# con68k-led.net
KiCad netlist of a schematic drawn in EAGLE
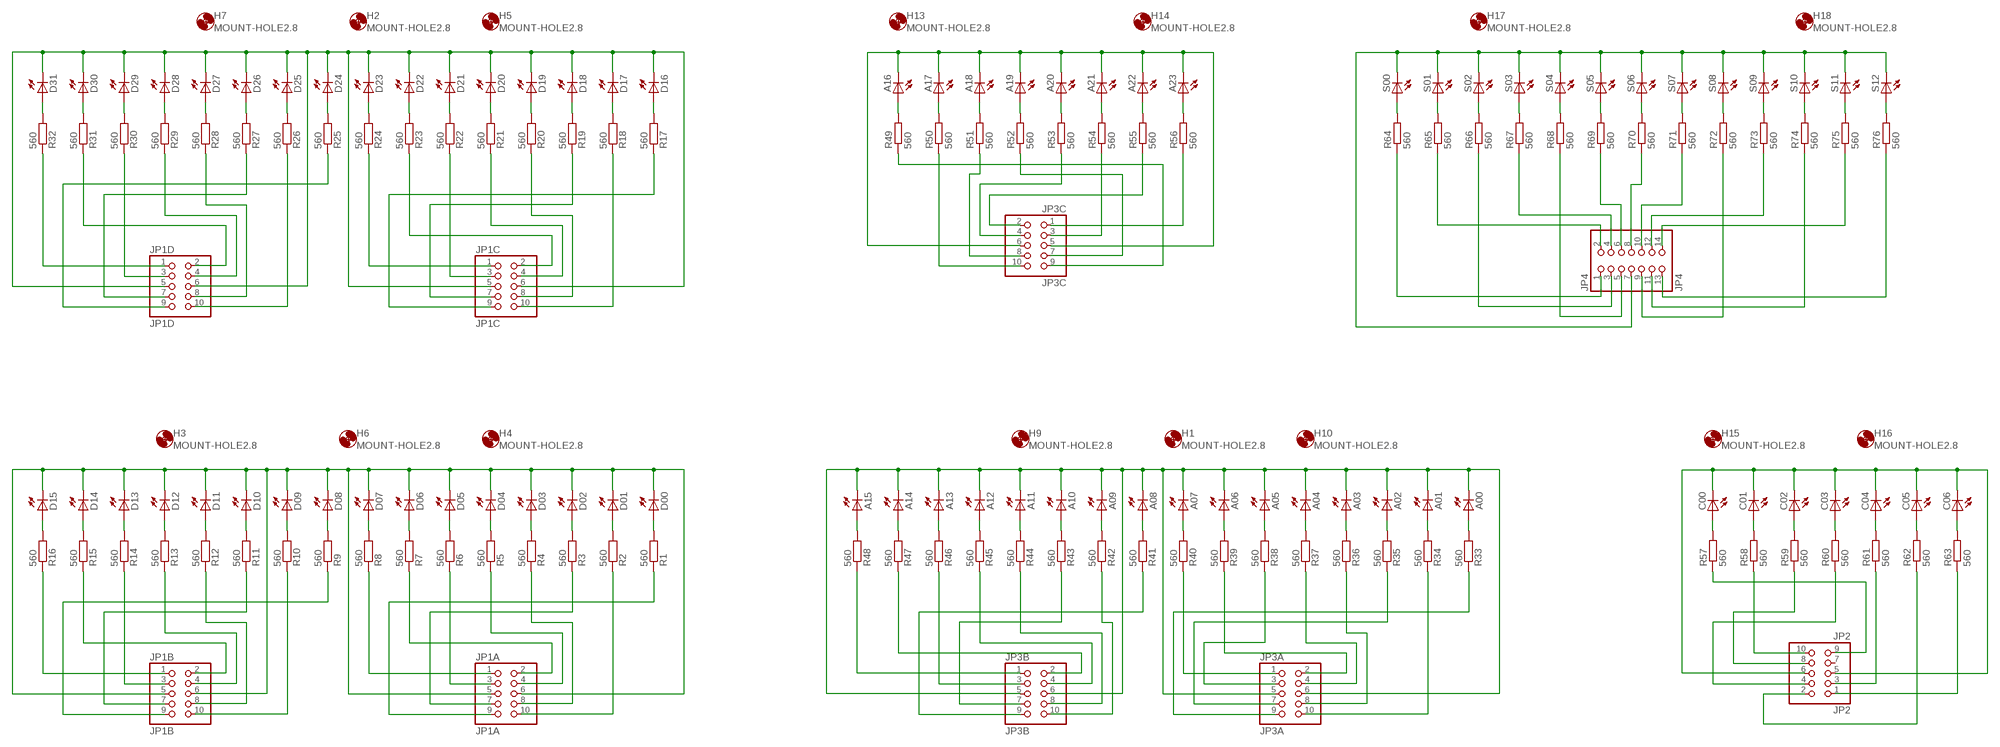
[diagram p0: schematic, sheet 1]

(export (version "E")
  (design (tool "Eeschema 10.0.6"))
  (components
    (comp (ref "A00")
      (value "LED5MM")
      (footprint "eagle-import:LED5MM")
      (libsource (lib "eagle-import") (part "LED5MM"))
    )
    (comp (ref "A01")
      (value "LED5MM")
      (footprint "eagle-import:LED5MM")
      (libsource (lib "eagle-import") (part "LED5MM"))
    )
    (comp (ref "A02")
      (value "LED5MM")
      (footprint "eagle-import:LED5MM")
      (libsource (lib "eagle-import") (part "LED5MM"))
    )
    (comp (ref "A03")
      (value "LED5MM")
      (footprint "eagle-import:LED5MM")
      (libsource (lib "eagle-import") (part "LED5MM"))
    )
    (comp (ref "A04")
      (value "LED5MM")
      (footprint "eagle-import:LED5MM")
      (libsource (lib "eagle-import") (part "LED5MM"))
    )
    (comp (ref "A05")
      (value "LED5MM")
      (footprint "eagle-import:LED5MM")
      (libsource (lib "eagle-import") (part "LED5MM"))
    )
    (comp (ref "A06")
      (value "LED5MM")
      (footprint "eagle-import:LED5MM")
      (libsource (lib "eagle-import") (part "LED5MM"))
    )
    (comp (ref "A07")
      (value "LED5MM")
      (footprint "eagle-import:LED5MM")
      (libsource (lib "eagle-import") (part "LED5MM"))
    )
    (comp (ref "A08")
      (value "LED5MM")
      (footprint "eagle-import:LED5MM")
      (libsource (lib "eagle-import") (part "LED5MM"))
    )
    (comp (ref "A09")
      (value "LED5MM")
      (footprint "eagle-import:LED5MM")
      (libsource (lib "eagle-import") (part "LED5MM"))
    )
    (comp (ref "A10")
      (value "LED5MM")
      (footprint "eagle-import:LED5MM")
      (libsource (lib "eagle-import") (part "LED5MM"))
    )
    (comp (ref "A11")
      (value "LED5MM")
      (footprint "eagle-import:LED5MM")
      (libsource (lib "eagle-import") (part "LED5MM"))
    )
    (comp (ref "A12")
      (value "LED5MM")
      (footprint "eagle-import:LED5MM")
      (libsource (lib "eagle-import") (part "LED5MM"))
    )
    (comp (ref "A13")
      (value "LED5MM")
      (footprint "eagle-import:LED5MM")
      (libsource (lib "eagle-import") (part "LED5MM"))
    )
    (comp (ref "A14")
      (value "LED5MM")
      (footprint "eagle-import:LED5MM")
      (libsource (lib "eagle-import") (part "LED5MM"))
    )
    (comp (ref "A15")
      (value "LED5MM")
      (footprint "eagle-import:LED5MM")
      (libsource (lib "eagle-import") (part "LED5MM"))
    )
    (comp (ref "A16")
      (value "LED5MM")
      (footprint "eagle-import:LED5MM")
      (libsource (lib "eagle-import") (part "LED5MM"))
    )
    (comp (ref "A17")
      (value "LED5MM")
      (footprint "eagle-import:LED5MM")
      (libsource (lib "eagle-import") (part "LED5MM"))
    )
    (comp (ref "A18")
      (value "LED5MM")
      (footprint "eagle-import:LED5MM")
      (libsource (lib "eagle-import") (part "LED5MM"))
    )
    (comp (ref "A19")
      (value "LED5MM")
      (footprint "eagle-import:LED5MM")
      (libsource (lib "eagle-import") (part "LED5MM"))
    )
    (comp (ref "A20")
      (value "LED5MM")
      (footprint "eagle-import:LED5MM")
      (libsource (lib "eagle-import") (part "LED5MM"))
    )
    (comp (ref "A21")
      (value "LED5MM")
      (footprint "eagle-import:LED5MM")
      (libsource (lib "eagle-import") (part "LED5MM"))
    )
    (comp (ref "A22")
      (value "LED5MM")
      (footprint "eagle-import:LED5MM")
      (libsource (lib "eagle-import") (part "LED5MM"))
    )
    (comp (ref "A23")
      (value "LED5MM")
      (footprint "eagle-import:LED5MM")
      (libsource (lib "eagle-import") (part "LED5MM"))
    )
    (comp (ref "C00")
      (value "LED5MM")
      (footprint "eagle-import:LED5MM")
      (libsource (lib "eagle-import") (part "LED5MM"))
    )
    (comp (ref "C01")
      (value "LED5MM")
      (footprint "eagle-import:LED5MM")
      (libsource (lib "eagle-import") (part "LED5MM"))
    )
    (comp (ref "C02")
      (value "LED5MM")
      (footprint "eagle-import:LED5MM")
      (libsource (lib "eagle-import") (part "LED5MM"))
    )
    (comp (ref "C03")
      (value "LED5MM")
      (footprint "eagle-import:LED5MM")
      (libsource (lib "eagle-import") (part "LED5MM"))
    )
    (comp (ref "C04")
      (value "LED5MM")
      (footprint "eagle-import:LED5MM")
      (libsource (lib "eagle-import") (part "LED5MM"))
    )
    (comp (ref "C05")
      (value "LED5MM")
      (footprint "eagle-import:LED5MM")
      (libsource (lib "eagle-import") (part "LED5MM"))
    )
    (comp (ref "C06")
      (value "LED5MM")
      (footprint "eagle-import:LED5MM")
      (libsource (lib "eagle-import") (part "LED5MM"))
    )
    (comp (ref "D00")
      (value "LED5MM")
      (footprint "eagle-import:LED5MM")
      (libsource (lib "eagle-import") (part "LED5MM"))
    )
    (comp (ref "D01")
      (value "LED5MM")
      (footprint "eagle-import:LED5MM")
      (libsource (lib "eagle-import") (part "LED5MM"))
    )
    (comp (ref "D02")
      (value "LED5MM")
      (footprint "eagle-import:LED5MM")
      (libsource (lib "eagle-import") (part "LED5MM"))
    )
    (comp (ref "D03")
      (value "LED5MM")
      (footprint "eagle-import:LED5MM")
      (libsource (lib "eagle-import") (part "LED5MM"))
    )
    (comp (ref "D04")
      (value "LED5MM")
      (footprint "eagle-import:LED5MM")
      (libsource (lib "eagle-import") (part "LED5MM"))
    )
    (comp (ref "D05")
      (value "LED5MM")
      (footprint "eagle-import:LED5MM")
      (libsource (lib "eagle-import") (part "LED5MM"))
    )
    (comp (ref "D06")
      (value "LED5MM")
      (footprint "eagle-import:LED5MM")
      (libsource (lib "eagle-import") (part "LED5MM"))
    )
    (comp (ref "D07")
      (value "LED5MM")
      (footprint "eagle-import:LED5MM")
      (libsource (lib "eagle-import") (part "LED5MM"))
    )
    (comp (ref "D08")
      (value "LED5MM")
      (footprint "eagle-import:LED5MM")
      (libsource (lib "eagle-import") (part "LED5MM"))
    )
    (comp (ref "D09")
      (value "LED5MM")
      (footprint "eagle-import:LED5MM")
      (libsource (lib "eagle-import") (part "LED5MM"))
    )
    (comp (ref "D10")
      (value "LED5MM")
      (footprint "eagle-import:LED5MM")
      (libsource (lib "eagle-import") (part "LED5MM"))
    )
    (comp (ref "D11")
      (value "LED5MM")
      (footprint "eagle-import:LED5MM")
      (libsource (lib "eagle-import") (part "LED5MM"))
    )
    (comp (ref "D12")
      (value "LED5MM")
      (footprint "eagle-import:LED5MM")
      (libsource (lib "eagle-import") (part "LED5MM"))
    )
    (comp (ref "D13")
      (value "LED5MM")
      (footprint "eagle-import:LED5MM")
      (libsource (lib "eagle-import") (part "LED5MM"))
    )
    (comp (ref "D14")
      (value "LED5MM")
      (footprint "eagle-import:LED5MM")
      (libsource (lib "eagle-import") (part "LED5MM"))
    )
    (comp (ref "D15")
      (value "LED5MM")
      (footprint "eagle-import:LED5MM")
      (libsource (lib "eagle-import") (part "LED5MM"))
    )
    (comp (ref "D16")
      (value "LED5MM")
      (footprint "eagle-import:LED5MM")
      (libsource (lib "eagle-import") (part "LED5MM"))
    )
    (comp (ref "D17")
      (value "LED5MM")
      (footprint "eagle-import:LED5MM")
      (libsource (lib "eagle-import") (part "LED5MM"))
    )
    (comp (ref "D18")
      (value "LED5MM")
      (footprint "eagle-import:LED5MM")
      (libsource (lib "eagle-import") (part "LED5MM"))
    )
    (comp (ref "D19")
      (value "LED5MM")
      (footprint "eagle-import:LED5MM")
      (libsource (lib "eagle-import") (part "LED5MM"))
    )
    (comp (ref "D20")
      (value "LED5MM")
      (footprint "eagle-import:LED5MM")
      (libsource (lib "eagle-import") (part "LED5MM"))
    )
    (comp (ref "D21")
      (value "LED5MM")
      (footprint "eagle-import:LED5MM")
      (libsource (lib "eagle-import") (part "LED5MM"))
    )
    (comp (ref "D22")
      (value "LED5MM")
      (footprint "eagle-import:LED5MM")
      (libsource (lib "eagle-import") (part "LED5MM"))
    )
    (comp (ref "D23")
      (value "LED5MM")
      (footprint "eagle-import:LED5MM")
      (libsource (lib "eagle-import") (part "LED5MM"))
    )
    (comp (ref "D24")
      (value "LED5MM")
      (footprint "eagle-import:LED5MM")
      (libsource (lib "eagle-import") (part "LED5MM"))
    )
    (comp (ref "D25")
      (value "LED5MM")
      (footprint "eagle-import:LED5MM")
      (libsource (lib "eagle-import") (part "LED5MM"))
    )
    (comp (ref "D26")
      (value "LED5MM")
      (footprint "eagle-import:LED5MM")
      (libsource (lib "eagle-import") (part "LED5MM"))
    )
    (comp (ref "D27")
      (value "LED5MM")
      (footprint "eagle-import:LED5MM")
      (libsource (lib "eagle-import") (part "LED5MM"))
    )
    (comp (ref "D28")
      (value "LED5MM")
      (footprint "eagle-import:LED5MM")
      (libsource (lib "eagle-import") (part "LED5MM"))
    )
    (comp (ref "D29")
      (value "LED5MM")
      (footprint "eagle-import:LED5MM")
      (libsource (lib "eagle-import") (part "LED5MM"))
    )
    (comp (ref "D30")
      (value "LED5MM")
      (footprint "eagle-import:LED5MM")
      (libsource (lib "eagle-import") (part "LED5MM"))
    )
    (comp (ref "D31")
      (value "LED5MM")
      (footprint "eagle-import:LED5MM")
      (libsource (lib "eagle-import") (part "LED5MM"))
    )
    (comp (ref "H1")
      (value "MOUNT-HOLE2.8")
      (footprint "eagle-import:2,8")
      (libsource (lib "eagle-import") (part "MOUNT-HOLE2.8"))
    )
    (comp (ref "H2")
      (value "MOUNT-HOLE2.8")
      (footprint "eagle-import:2,8")
      (libsource (lib "eagle-import") (part "MOUNT-HOLE2.8"))
    )
    (comp (ref "H3")
      (value "MOUNT-HOLE2.8")
      (footprint "eagle-import:2,8")
      (libsource (lib "eagle-import") (part "MOUNT-HOLE2.8"))
    )
    (comp (ref "H4")
      (value "MOUNT-HOLE2.8")
      (footprint "eagle-import:2,8")
      (libsource (lib "eagle-import") (part "MOUNT-HOLE2.8"))
    )
    (comp (ref "H5")
      (value "MOUNT-HOLE2.8")
      (footprint "eagle-import:2,8")
      (libsource (lib "eagle-import") (part "MOUNT-HOLE2.8"))
    )
    (comp (ref "H6")
      (value "MOUNT-HOLE2.8")
      (footprint "eagle-import:2,8")
      (libsource (lib "eagle-import") (part "MOUNT-HOLE2.8"))
    )
    (comp (ref "H7")
      (value "MOUNT-HOLE2.8")
      (footprint "eagle-import:2,8")
      (libsource (lib "eagle-import") (part "MOUNT-HOLE2.8"))
    )
    (comp (ref "H9")
      (value "MOUNT-HOLE2.8")
      (footprint "eagle-import:2,8")
      (libsource (lib "eagle-import") (part "MOUNT-HOLE2.8"))
    )
    (comp (ref "H10")
      (value "MOUNT-HOLE2.8")
      (footprint "eagle-import:2,8")
      (libsource (lib "eagle-import") (part "MOUNT-HOLE2.8"))
    )
    (comp (ref "H13")
      (value "MOUNT-HOLE2.8")
      (footprint "eagle-import:2,8")
      (libsource (lib "eagle-import") (part "MOUNT-HOLE2.8"))
    )
    (comp (ref "H14")
      (value "MOUNT-HOLE2.8")
      (footprint "eagle-import:2,8")
      (libsource (lib "eagle-import") (part "MOUNT-HOLE2.8"))
    )
    (comp (ref "H15")
      (value "MOUNT-HOLE2.8")
      (footprint "eagle-import:2,8")
      (libsource (lib "eagle-import") (part "MOUNT-HOLE2.8"))
    )
    (comp (ref "H16")
      (value "MOUNT-HOLE2.8")
      (footprint "eagle-import:2,8")
      (libsource (lib "eagle-import") (part "MOUNT-HOLE2.8"))
    )
    (comp (ref "H17")
      (value "MOUNT-HOLE2.8")
      (footprint "eagle-import:2,8")
      (libsource (lib "eagle-import") (part "MOUNT-HOLE2.8"))
    )
    (comp (ref "H18")
      (value "MOUNT-HOLE2.8")
      (footprint "eagle-import:2,8")
      (libsource (lib "eagle-import") (part "MOUNT-HOLE2.8"))
    )
    (comp (ref "JP1A")
      (value "JP1A")
      (footprint "eagle-import:2X05")
      (libsource (lib "eagle-import") (part "PINHD-2X5"))
    )
    (comp (ref "JP1B")
      (value "JP1B")
      (footprint "eagle-import:2X05")
      (libsource (lib "eagle-import") (part "PINHD-2X5"))
    )
    (comp (ref "JP1C")
      (value "JP1C")
      (footprint "eagle-import:2X05")
      (libsource (lib "eagle-import") (part "PINHD-2X5"))
    )
    (comp (ref "JP1D")
      (value "JP1D")
      (footprint "eagle-import:2X05")
      (libsource (lib "eagle-import") (part "PINHD-2X5"))
    )
    (comp (ref "JP2")
      (value "JP2")
      (footprint "eagle-import:2X05")
      (libsource (lib "eagle-import") (part "PINHD-2X5"))
    )
    (comp (ref "JP3A")
      (value "JP3A")
      (footprint "eagle-import:2X05")
      (libsource (lib "eagle-import") (part "PINHD-2X5"))
    )
    (comp (ref "JP3B")
      (value "JP3B")
      (footprint "eagle-import:2X05")
      (libsource (lib "eagle-import") (part "PINHD-2X5"))
    )
    (comp (ref "JP3C")
      (value "JP3C")
      (footprint "eagle-import:2X05")
      (libsource (lib "eagle-import") (part "PINHD-2X5"))
    )
    (comp (ref "JP4")
      (value "JP4")
      (footprint "eagle-import:2X07")
      (libsource (lib "eagle-import") (part "PINHD-2X7"))
    )
    (comp (ref "R1")
      (value "560")
      (footprint "eagle-import:0204_7")
      (libsource (lib "eagle-import") (part "R-EU_0204/7"))
    )
    (comp (ref "R2")
      (value "560")
      (footprint "eagle-import:0204_7")
      (libsource (lib "eagle-import") (part "R-EU_0204/7"))
    )
    (comp (ref "R3")
      (value "560")
      (footprint "eagle-import:0204_7")
      (libsource (lib "eagle-import") (part "R-EU_0204/7"))
    )
    (comp (ref "R4")
      (value "560")
      (footprint "eagle-import:0204_7")
      (libsource (lib "eagle-import") (part "R-EU_0204/7"))
    )
    (comp (ref "R5")
      (value "560")
      (footprint "eagle-import:0204_7")
      (libsource (lib "eagle-import") (part "R-EU_0204/7"))
    )
    (comp (ref "R6")
      (value "560")
      (footprint "eagle-import:0204_7")
      (libsource (lib "eagle-import") (part "R-EU_0204/7"))
    )
    (comp (ref "R7")
      (value "560")
      (footprint "eagle-import:0204_7")
      (libsource (lib "eagle-import") (part "R-EU_0204/7"))
    )
    (comp (ref "R8")
      (value "560")
      (footprint "eagle-import:0204_7")
      (libsource (lib "eagle-import") (part "R-EU_0204/7"))
    )
    (comp (ref "R9")
      (value "560")
      (footprint "eagle-import:0204_7")
      (libsource (lib "eagle-import") (part "R-EU_0204/7"))
    )
    (comp (ref "R10")
      (value "560")
      (footprint "eagle-import:0204_7")
      (libsource (lib "eagle-import") (part "R-EU_0204/7"))
    )
    (comp (ref "R11")
      (value "560")
      (footprint "eagle-import:0204_7")
      (libsource (lib "eagle-import") (part "R-EU_0204/7"))
    )
    (comp (ref "R12")
      (value "560")
      (footprint "eagle-import:0204_7")
      (libsource (lib "eagle-import") (part "R-EU_0204/7"))
    )
    (comp (ref "R13")
      (value "560")
      (footprint "eagle-import:0204_7")
      (libsource (lib "eagle-import") (part "R-EU_0204/7"))
    )
    (comp (ref "R14")
      (value "560")
      (footprint "eagle-import:0204_7")
      (libsource (lib "eagle-import") (part "R-EU_0204/7"))
    )
    (comp (ref "R15")
      (value "560")
      (footprint "eagle-import:0204_7")
      (libsource (lib "eagle-import") (part "R-EU_0204/7"))
    )
    (comp (ref "R16")
      (value "560")
      (footprint "eagle-import:0204_7")
      (libsource (lib "eagle-import") (part "R-EU_0204/7"))
    )
    (comp (ref "R17")
      (value "560")
      (footprint "eagle-import:0204_7")
      (libsource (lib "eagle-import") (part "R-EU_0204/7"))
    )
    (comp (ref "R18")
      (value "560")
      (footprint "eagle-import:0204_7")
      (libsource (lib "eagle-import") (part "R-EU_0204/7"))
    )
    (comp (ref "R19")
      (value "560")
      (footprint "eagle-import:0204_7")
      (libsource (lib "eagle-import") (part "R-EU_0204/7"))
    )
    (comp (ref "R20")
      (value "560")
      (footprint "eagle-import:0204_7")
      (libsource (lib "eagle-import") (part "R-EU_0204/7"))
    )
    (comp (ref "R21")
      (value "560")
      (footprint "eagle-import:0204_7")
      (libsource (lib "eagle-import") (part "R-EU_0204/7"))
    )
    (comp (ref "R22")
      (value "560")
      (footprint "eagle-import:0204_7")
      (libsource (lib "eagle-import") (part "R-EU_0204/7"))
    )
    (comp (ref "R23")
      (value "560")
      (footprint "eagle-import:0204_7")
      (libsource (lib "eagle-import") (part "R-EU_0204/7"))
    )
    (comp (ref "R24")
      (value "560")
      (footprint "eagle-import:0204_7")
      (libsource (lib "eagle-import") (part "R-EU_0204/7"))
    )
    (comp (ref "R25")
      (value "560")
      (footprint "eagle-import:0204_7")
      (libsource (lib "eagle-import") (part "R-EU_0204/7"))
    )
    (comp (ref "R26")
      (value "560")
      (footprint "eagle-import:0204_7")
      (libsource (lib "eagle-import") (part "R-EU_0204/7"))
    )
    (comp (ref "R27")
      (value "560")
      (footprint "eagle-import:0204_7")
      (libsource (lib "eagle-import") (part "R-EU_0204/7"))
    )
    (comp (ref "R28")
      (value "560")
      (footprint "eagle-import:0204_7")
      (libsource (lib "eagle-import") (part "R-EU_0204/7"))
    )
    (comp (ref "R29")
      (value "560")
      (footprint "eagle-import:0204_7")
      (libsource (lib "eagle-import") (part "R-EU_0204/7"))
    )
    (comp (ref "R30")
      (value "560")
      (footprint "eagle-import:0204_7")
      (libsource (lib "eagle-import") (part "R-EU_0204/7"))
    )
    (comp (ref "R31")
      (value "560")
      (footprint "eagle-import:0204_7")
      (libsource (lib "eagle-import") (part "R-EU_0204/7"))
    )
    (comp (ref "R32")
      (value "560")
      (footprint "eagle-import:0204_7")
      (libsource (lib "eagle-import") (part "R-EU_0204/7"))
    )
    (comp (ref "R33")
      (value "560")
      (footprint "eagle-import:0204_7")
      (libsource (lib "eagle-import") (part "R-EU_0204/7"))
    )
    (comp (ref "R34")
      (value "560")
      (footprint "eagle-import:0204_7")
      (libsource (lib "eagle-import") (part "R-EU_0204/7"))
    )
    (comp (ref "R35")
      (value "560")
      (footprint "eagle-import:0204_7")
      (libsource (lib "eagle-import") (part "R-EU_0204/7"))
    )
    (comp (ref "R36")
      (value "560")
      (footprint "eagle-import:0204_7")
      (libsource (lib "eagle-import") (part "R-EU_0204/7"))
    )
    (comp (ref "R37")
      (value "560")
      (footprint "eagle-import:0204_7")
      (libsource (lib "eagle-import") (part "R-EU_0204/7"))
    )
    (comp (ref "R38")
      (value "560")
      (footprint "eagle-import:0204_7")
      (libsource (lib "eagle-import") (part "R-EU_0204/7"))
    )
    (comp (ref "R39")
      (value "560")
      (footprint "eagle-import:0204_7")
      (libsource (lib "eagle-import") (part "R-EU_0204/7"))
    )
    (comp (ref "R40")
      (value "560")
      (footprint "eagle-import:0204_7")
      (libsource (lib "eagle-import") (part "R-EU_0204/7"))
    )
    (comp (ref "R41")
      (value "560")
      (footprint "eagle-import:0204_7")
      (libsource (lib "eagle-import") (part "R-EU_0204/7"))
    )
    (comp (ref "R42")
      (value "560")
      (footprint "eagle-import:0204_7")
      (libsource (lib "eagle-import") (part "R-EU_0204/7"))
    )
    (comp (ref "R43")
      (value "560")
      (footprint "eagle-import:0204_7")
      (libsource (lib "eagle-import") (part "R-EU_0204/7"))
    )
    (comp (ref "R44")
      (value "560")
      (footprint "eagle-import:0204_7")
      (libsource (lib "eagle-import") (part "R-EU_0204/7"))
    )
    (comp (ref "R45")
      (value "560")
      (footprint "eagle-import:0204_7")
      (libsource (lib "eagle-import") (part "R-EU_0204/7"))
    )
    (comp (ref "R46")
      (value "560")
      (footprint "eagle-import:0204_7")
      (libsource (lib "eagle-import") (part "R-EU_0204/7"))
    )
    (comp (ref "R47")
      (value "560")
      (footprint "eagle-import:0204_7")
      (libsource (lib "eagle-import") (part "R-EU_0204/7"))
    )
    (comp (ref "R48")
      (value "560")
      (footprint "eagle-import:0204_7")
      (libsource (lib "eagle-import") (part "R-EU_0204/7"))
    )
    (comp (ref "R49")
      (value "560")
      (footprint "eagle-import:0204_7")
      (libsource (lib "eagle-import") (part "R-EU_0204/7"))
    )
    (comp (ref "R50")
      (value "560")
      (footprint "eagle-import:0204_7")
      (libsource (lib "eagle-import") (part "R-EU_0204/7"))
    )
    (comp (ref "R51")
      (value "560")
      (footprint "eagle-import:0204_7")
      (libsource (lib "eagle-import") (part "R-EU_0204/7"))
    )
    (comp (ref "R52")
      (value "560")
      (footprint "eagle-import:0204_7")
      (libsource (lib "eagle-import") (part "R-EU_0204/7"))
    )
    (comp (ref "R53")
      (value "560")
      (footprint "eagle-import:0204_7")
      (libsource (lib "eagle-import") (part "R-EU_0204/7"))
    )
    (comp (ref "R54")
      (value "560")
      (footprint "eagle-import:0204_7")
      (libsource (lib "eagle-import") (part "R-EU_0204/7"))
    )
    (comp (ref "R55")
      (value "560")
      (footprint "eagle-import:0204_7")
      (libsource (lib "eagle-import") (part "R-EU_0204/7"))
    )
    (comp (ref "R56")
      (value "560")
      (footprint "eagle-import:0204_7")
      (libsource (lib "eagle-import") (part "R-EU_0204/7"))
    )
    (comp (ref "R57")
      (value "560")
      (footprint "eagle-import:0204_7")
      (libsource (lib "eagle-import") (part "R-EU_0204/7"))
    )
    (comp (ref "R58")
      (value "560")
      (footprint "eagle-import:0204_7")
      (libsource (lib "eagle-import") (part "R-EU_0204/7"))
    )
    (comp (ref "R59")
      (value "560")
      (footprint "eagle-import:0204_7")
      (libsource (lib "eagle-import") (part "R-EU_0204/7"))
    )
    (comp (ref "R60")
      (value "560")
      (footprint "eagle-import:0204_7")
      (libsource (lib "eagle-import") (part "R-EU_0204/7"))
    )
    (comp (ref "R61")
      (value "560")
      (footprint "eagle-import:0204_7")
      (libsource (lib "eagle-import") (part "R-EU_0204/7"))
    )
    (comp (ref "R62")
      (value "560")
      (footprint "eagle-import:0204_7")
      (libsource (lib "eagle-import") (part "R-EU_0204/7"))
    )
    (comp (ref "R63")
      (value "560")
      (footprint "eagle-import:0204_7")
      (libsource (lib "eagle-import") (part "R-EU_0204/7"))
    )
    (comp (ref "R64")
      (value "560")
      (footprint "eagle-import:0204_7")
      (libsource (lib "eagle-import") (part "R-EU_0204/7"))
    )
    (comp (ref "R65")
      (value "560")
      (footprint "eagle-import:0204_7")
      (libsource (lib "eagle-import") (part "R-EU_0204/7"))
    )
    (comp (ref "R66")
      (value "560")
      (footprint "eagle-import:0204_7")
      (libsource (lib "eagle-import") (part "R-EU_0204/7"))
    )
    (comp (ref "R67")
      (value "560")
      (footprint "eagle-import:0204_7")
      (libsource (lib "eagle-import") (part "R-EU_0204/7"))
    )
    (comp (ref "R68")
      (value "560")
      (footprint "eagle-import:0204_7")
      (libsource (lib "eagle-import") (part "R-EU_0204/7"))
    )
    (comp (ref "R69")
      (value "560")
      (footprint "eagle-import:0204_7")
      (libsource (lib "eagle-import") (part "R-EU_0204/7"))
    )
    (comp (ref "R70")
      (value "560")
      (footprint "eagle-import:0204_7")
      (libsource (lib "eagle-import") (part "R-EU_0204/7"))
    )
    (comp (ref "R71")
      (value "560")
      (footprint "eagle-import:0204_7")
      (libsource (lib "eagle-import") (part "R-EU_0204/7"))
    )
    (comp (ref "R72")
      (value "560")
      (footprint "eagle-import:0204_7")
      (libsource (lib "eagle-import") (part "R-EU_0204/7"))
    )
    (comp (ref "R73")
      (value "560")
      (footprint "eagle-import:0204_7")
      (libsource (lib "eagle-import") (part "R-EU_0204/7"))
    )
    (comp (ref "R74")
      (value "560")
      (footprint "eagle-import:0204_7")
      (libsource (lib "eagle-import") (part "R-EU_0204/7"))
    )
    (comp (ref "R75")
      (value "560")
      (footprint "eagle-import:0204_7")
      (libsource (lib "eagle-import") (part "R-EU_0204/7"))
    )
    (comp (ref "R76")
      (value "560")
      (footprint "eagle-import:0204_7")
      (libsource (lib "eagle-import") (part "R-EU_0204/7"))
    )
    (comp (ref "S00")
      (value "LED5MM")
      (footprint "eagle-import:LED5MM")
      (libsource (lib "eagle-import") (part "LED5MM"))
    )
    (comp (ref "S01")
      (value "LED5MM")
      (footprint "eagle-import:LED5MM")
      (libsource (lib "eagle-import") (part "LED5MM"))
    )
    (comp (ref "S02")
      (value "LED5MM")
      (footprint "eagle-import:LED5MM")
      (libsource (lib "eagle-import") (part "LED5MM"))
    )
    (comp (ref "S03")
      (value "LED5MM")
      (footprint "eagle-import:LED5MM")
      (libsource (lib "eagle-import") (part "LED5MM"))
    )
    (comp (ref "S04")
      (value "LED5MM")
      (footprint "eagle-import:LED5MM")
      (libsource (lib "eagle-import") (part "LED5MM"))
    )
    (comp (ref "S05")
      (value "LED5MM")
      (footprint "eagle-import:LED5MM")
      (libsource (lib "eagle-import") (part "LED5MM"))
    )
    (comp (ref "S06")
      (value "LED5MM")
      (footprint "eagle-import:LED5MM")
      (libsource (lib "eagle-import") (part "LED5MM"))
    )
    (comp (ref "S07")
      (value "LED5MM")
      (footprint "eagle-import:LED5MM")
      (libsource (lib "eagle-import") (part "LED5MM"))
    )
    (comp (ref "S08")
      (value "LED5MM")
      (footprint "eagle-import:LED5MM")
      (libsource (lib "eagle-import") (part "LED5MM"))
    )
    (comp (ref "S09")
      (value "LED5MM")
      (footprint "eagle-import:LED5MM")
      (libsource (lib "eagle-import") (part "LED5MM"))
    )
    (comp (ref "S10")
      (value "LED5MM")
      (footprint "eagle-import:LED5MM")
      (libsource (lib "eagle-import") (part "LED5MM"))
    )
    (comp (ref "S11")
      (value "LED5MM")
      (footprint "eagle-import:LED5MM")
      (libsource (lib "eagle-import") (part "LED5MM"))
    )
    (comp (ref "S12")
      (value "LED5MM")
      (footprint "eagle-import:LED5MM")
      (libsource (lib "eagle-import") (part "LED5MM"))
    )
  )
  (nets
    (net (code "1") (name "Net-(A00-C)") (class "Default")
      (node (ref "A00") (pin "K") (pinfunction "C_K") (pintype "passive"))
      (node (ref "A01") (pin "K") (pinfunction "C_K") (pintype "passive"))
      (node (ref "A02") (pin "K") (pinfunction "C_K") (pintype "passive"))
      (node (ref "A03") (pin "K") (pinfunction "C_K") (pintype "passive"))
      (node (ref "A04") (pin "K") (pinfunction "C_K") (pintype "passive"))
      (node (ref "A05") (pin "K") (pinfunction "C_K") (pintype "passive"))
      (node (ref "A06") (pin "K") (pinfunction "C_K") (pintype "passive"))
      (node (ref "A07") (pin "K") (pinfunction "C_K") (pintype "passive"))
      (node (ref "A08") (pin "K") (pinfunction "C_K") (pintype "passive"))
      (node (ref "A09") (pin "K") (pinfunction "C_K") (pintype "passive"))
      (node (ref "A10") (pin "K") (pinfunction "C_K") (pintype "passive"))
      (node (ref "A11") (pin "K") (pinfunction "C_K") (pintype "passive"))
      (node (ref "A12") (pin "K") (pinfunction "C_K") (pintype "passive"))
      (node (ref "A13") (pin "K") (pinfunction "C_K") (pintype "passive"))
      (node (ref "A14") (pin "K") (pinfunction "C_K") (pintype "passive"))
      (node (ref "A15") (pin "K") (pinfunction "C_K") (pintype "passive"))
      (node (ref "JP3A") (pin "5") (pinfunction "5_5") (pintype "passive"))
      (node (ref "JP3A") (pin "6") (pinfunction "6_6") (pintype "passive"))
      (node (ref "JP3B") (pin "5") (pinfunction "5_5") (pintype "passive"))
      (node (ref "JP3B") (pin "6") (pinfunction "6_6") (pintype "passive"))
    )
    (net (code "2") (name "Net-(A00-PadA)") (class "Default")
      (node (ref "A00") (pin "A") (pinfunction "A_A") (pintype "passive"))
      (node (ref "R33") (pin "2") (pinfunction "2_2") (pintype "passive"))
    )
    (net (code "3") (name "Net-(A01-PadA)") (class "Default")
      (node (ref "A01") (pin "A") (pinfunction "A_A") (pintype "passive"))
      (node (ref "R34") (pin "2") (pinfunction "2_2") (pintype "passive"))
    )
    (net (code "4") (name "Net-(A02-PadA)") (class "Default")
      (node (ref "A02") (pin "A") (pinfunction "A_A") (pintype "passive"))
      (node (ref "R35") (pin "2") (pinfunction "2_2") (pintype "passive"))
    )
    (net (code "5") (name "Net-(A03-PadA)") (class "Default")
      (node (ref "A03") (pin "A") (pinfunction "A_A") (pintype "passive"))
      (node (ref "R36") (pin "2") (pinfunction "2_2") (pintype "passive"))
    )
    (net (code "6") (name "Net-(A04-PadA)") (class "Default")
      (node (ref "A04") (pin "A") (pinfunction "A_A") (pintype "passive"))
      (node (ref "R37") (pin "2") (pinfunction "2_2") (pintype "passive"))
    )
    (net (code "7") (name "Net-(A05-PadA)") (class "Default")
      (node (ref "A05") (pin "A") (pinfunction "A_A") (pintype "passive"))
      (node (ref "R38") (pin "2") (pinfunction "2_2") (pintype "passive"))
    )
    (net (code "8") (name "Net-(A06-PadA)") (class "Default")
      (node (ref "A06") (pin "A") (pinfunction "A_A") (pintype "passive"))
      (node (ref "R39") (pin "2") (pinfunction "2_2") (pintype "passive"))
    )
    (net (code "9") (name "Net-(A07-PadA)") (class "Default")
      (node (ref "A07") (pin "A") (pinfunction "A_A") (pintype "passive"))
      (node (ref "R40") (pin "2") (pinfunction "2_2") (pintype "passive"))
    )
    (net (code "10") (name "Net-(A08-PadA)") (class "Default")
      (node (ref "A08") (pin "A") (pinfunction "A_A") (pintype "passive"))
      (node (ref "R41") (pin "2") (pinfunction "2_2") (pintype "passive"))
    )
    (net (code "11") (name "Net-(A09-PadA)") (class "Default")
      (node (ref "A09") (pin "A") (pinfunction "A_A") (pintype "passive"))
      (node (ref "R42") (pin "2") (pinfunction "2_2") (pintype "passive"))
    )
    (net (code "12") (name "Net-(A10-PadA)") (class "Default")
      (node (ref "A10") (pin "A") (pinfunction "A_A") (pintype "passive"))
      (node (ref "R43") (pin "2") (pinfunction "2_2") (pintype "passive"))
    )
    (net (code "13") (name "Net-(A11-PadA)") (class "Default")
      (node (ref "A11") (pin "A") (pinfunction "A_A") (pintype "passive"))
      (node (ref "R44") (pin "2") (pinfunction "2_2") (pintype "passive"))
    )
    (net (code "14") (name "Net-(A12-PadA)") (class "Default")
      (node (ref "A12") (pin "A") (pinfunction "A_A") (pintype "passive"))
      (node (ref "R45") (pin "2") (pinfunction "2_2") (pintype "passive"))
    )
    (net (code "15") (name "Net-(A13-PadA)") (class "Default")
      (node (ref "A13") (pin "A") (pinfunction "A_A") (pintype "passive"))
      (node (ref "R46") (pin "2") (pinfunction "2_2") (pintype "passive"))
    )
    (net (code "16") (name "Net-(A14-PadA)") (class "Default")
      (node (ref "A14") (pin "A") (pinfunction "A_A") (pintype "passive"))
      (node (ref "R47") (pin "2") (pinfunction "2_2") (pintype "passive"))
    )
    (net (code "17") (name "Net-(A15-PadA)") (class "Default")
      (node (ref "A15") (pin "A") (pinfunction "A_A") (pintype "passive"))
      (node (ref "R48") (pin "2") (pinfunction "2_2") (pintype "passive"))
    )
    (net (code "18") (name "Net-(A16-C)") (class "Default")
      (node (ref "A16") (pin "K") (pinfunction "C_K") (pintype "passive"))
      (node (ref "A17") (pin "K") (pinfunction "C_K") (pintype "passive"))
      (node (ref "A18") (pin "K") (pinfunction "C_K") (pintype "passive"))
      (node (ref "A19") (pin "K") (pinfunction "C_K") (pintype "passive"))
      (node (ref "A20") (pin "K") (pinfunction "C_K") (pintype "passive"))
      (node (ref "A21") (pin "K") (pinfunction "C_K") (pintype "passive"))
      (node (ref "A22") (pin "K") (pinfunction "C_K") (pintype "passive"))
      (node (ref "A23") (pin "K") (pinfunction "C_K") (pintype "passive"))
      (node (ref "JP3C") (pin "5") (pinfunction "5_5") (pintype "passive"))
      (node (ref "JP3C") (pin "6") (pinfunction "6_6") (pintype "passive"))
    )
    (net (code "19") (name "Net-(A16-PadA)") (class "Default")
      (node (ref "A16") (pin "A") (pinfunction "A_A") (pintype "passive"))
      (node (ref "R49") (pin "2") (pinfunction "2_2") (pintype "passive"))
    )
    (net (code "20") (name "Net-(A17-PadA)") (class "Default")
      (node (ref "A17") (pin "A") (pinfunction "A_A") (pintype "passive"))
      (node (ref "R50") (pin "2") (pinfunction "2_2") (pintype "passive"))
    )
    (net (code "21") (name "Net-(A18-PadA)") (class "Default")
      (node (ref "A18") (pin "A") (pinfunction "A_A") (pintype "passive"))
      (node (ref "R51") (pin "2") (pinfunction "2_2") (pintype "passive"))
    )
    (net (code "22") (name "Net-(A19-PadA)") (class "Default")
      (node (ref "A19") (pin "A") (pinfunction "A_A") (pintype "passive"))
      (node (ref "R52") (pin "2") (pinfunction "2_2") (pintype "passive"))
    )
    (net (code "23") (name "Net-(A20-PadA)") (class "Default")
      (node (ref "A20") (pin "A") (pinfunction "A_A") (pintype "passive"))
      (node (ref "R53") (pin "2") (pinfunction "2_2") (pintype "passive"))
    )
    (net (code "24") (name "Net-(A21-PadA)") (class "Default")
      (node (ref "A21") (pin "A") (pinfunction "A_A") (pintype "passive"))
      (node (ref "R54") (pin "2") (pinfunction "2_2") (pintype "passive"))
    )
    (net (code "25") (name "Net-(A22-PadA)") (class "Default")
      (node (ref "A22") (pin "A") (pinfunction "A_A") (pintype "passive"))
      (node (ref "R55") (pin "2") (pinfunction "2_2") (pintype "passive"))
    )
    (net (code "26") (name "Net-(A23-PadA)") (class "Default")
      (node (ref "A23") (pin "A") (pinfunction "A_A") (pintype "passive"))
      (node (ref "R56") (pin "2") (pinfunction "2_2") (pintype "passive"))
    )
    (net (code "27") (name "Net-(C00-C)") (class "Default")
      (node (ref "C00") (pin "K") (pinfunction "C_K") (pintype "passive"))
      (node (ref "C01") (pin "K") (pinfunction "C_K") (pintype "passive"))
      (node (ref "C02") (pin "K") (pinfunction "C_K") (pintype "passive"))
      (node (ref "C03") (pin "K") (pinfunction "C_K") (pintype "passive"))
      (node (ref "C04") (pin "K") (pinfunction "C_K") (pintype "passive"))
      (node (ref "C05") (pin "K") (pinfunction "C_K") (pintype "passive"))
      (node (ref "C06") (pin "K") (pinfunction "C_K") (pintype "passive"))
      (node (ref "JP2") (pin "5") (pinfunction "5_5") (pintype "passive"))
      (node (ref "JP2") (pin "6") (pinfunction "6_6") (pintype "passive"))
    )
    (net (code "28") (name "Net-(C00-PadA)") (class "Default")
      (node (ref "C00") (pin "A") (pinfunction "A_A") (pintype "passive"))
      (node (ref "R57") (pin "2") (pinfunction "2_2") (pintype "passive"))
    )
    (net (code "29") (name "Net-(C01-PadA)") (class "Default")
      (node (ref "C01") (pin "A") (pinfunction "A_A") (pintype "passive"))
      (node (ref "R58") (pin "2") (pinfunction "2_2") (pintype "passive"))
    )
    (net (code "30") (name "Net-(C02-PadA)") (class "Default")
      (node (ref "C02") (pin "A") (pinfunction "A_A") (pintype "passive"))
      (node (ref "R59") (pin "2") (pinfunction "2_2") (pintype "passive"))
    )
    (net (code "31") (name "Net-(C03-PadA)") (class "Default")
      (node (ref "C03") (pin "A") (pinfunction "A_A") (pintype "passive"))
      (node (ref "R60") (pin "2") (pinfunction "2_2") (pintype "passive"))
    )
    (net (code "32") (name "Net-(C04-PadA)") (class "Default")
      (node (ref "C04") (pin "A") (pinfunction "A_A") (pintype "passive"))
      (node (ref "R61") (pin "2") (pinfunction "2_2") (pintype "passive"))
    )
    (net (code "33") (name "Net-(C05-PadA)") (class "Default")
      (node (ref "C05") (pin "A") (pinfunction "A_A") (pintype "passive"))
      (node (ref "R62") (pin "2") (pinfunction "2_2") (pintype "passive"))
    )
    (net (code "34") (name "Net-(C06-PadA)") (class "Default")
      (node (ref "C06") (pin "A") (pinfunction "A_A") (pintype "passive"))
      (node (ref "R63") (pin "2") (pinfunction "2_2") (pintype "passive"))
    )
    (net (code "35") (name "Net-(D00-C)") (class "Default")
      (node (ref "D00") (pin "K") (pinfunction "C_K") (pintype "passive"))
      (node (ref "D01") (pin "K") (pinfunction "C_K") (pintype "passive"))
      (node (ref "D02") (pin "K") (pinfunction "C_K") (pintype "passive"))
      (node (ref "D03") (pin "K") (pinfunction "C_K") (pintype "passive"))
      (node (ref "D04") (pin "K") (pinfunction "C_K") (pintype "passive"))
      (node (ref "D05") (pin "K") (pinfunction "C_K") (pintype "passive"))
      (node (ref "D06") (pin "K") (pinfunction "C_K") (pintype "passive"))
      (node (ref "D07") (pin "K") (pinfunction "C_K") (pintype "passive"))
      (node (ref "D08") (pin "K") (pinfunction "C_K") (pintype "passive"))
      (node (ref "D09") (pin "K") (pinfunction "C_K") (pintype "passive"))
      (node (ref "D10") (pin "K") (pinfunction "C_K") (pintype "passive"))
      (node (ref "D11") (pin "K") (pinfunction "C_K") (pintype "passive"))
      (node (ref "D12") (pin "K") (pinfunction "C_K") (pintype "passive"))
      (node (ref "D13") (pin "K") (pinfunction "C_K") (pintype "passive"))
      (node (ref "D14") (pin "K") (pinfunction "C_K") (pintype "passive"))
      (node (ref "D15") (pin "K") (pinfunction "C_K") (pintype "passive"))
      (node (ref "JP1A") (pin "5") (pinfunction "5_5") (pintype "passive"))
      (node (ref "JP1A") (pin "6") (pinfunction "6_6") (pintype "passive"))
      (node (ref "JP1B") (pin "5") (pinfunction "5_5") (pintype "passive"))
      (node (ref "JP1B") (pin "6") (pinfunction "6_6") (pintype "passive"))
    )
    (net (code "36") (name "Net-(D00-PadA)") (class "Default")
      (node (ref "D00") (pin "A") (pinfunction "A_A") (pintype "passive"))
      (node (ref "R1") (pin "2") (pinfunction "2_2") (pintype "passive"))
    )
    (net (code "37") (name "Net-(D01-PadA)") (class "Default")
      (node (ref "D01") (pin "A") (pinfunction "A_A") (pintype "passive"))
      (node (ref "R2") (pin "2") (pinfunction "2_2") (pintype "passive"))
    )
    (net (code "38") (name "Net-(D02-PadA)") (class "Default")
      (node (ref "D02") (pin "A") (pinfunction "A_A") (pintype "passive"))
      (node (ref "R3") (pin "2") (pinfunction "2_2") (pintype "passive"))
    )
    (net (code "39") (name "Net-(D03-PadA)") (class "Default")
      (node (ref "D03") (pin "A") (pinfunction "A_A") (pintype "passive"))
      (node (ref "R4") (pin "2") (pinfunction "2_2") (pintype "passive"))
    )
    (net (code "40") (name "Net-(D04-PadA)") (class "Default")
      (node (ref "D04") (pin "A") (pinfunction "A_A") (pintype "passive"))
      (node (ref "R5") (pin "2") (pinfunction "2_2") (pintype "passive"))
    )
    (net (code "41") (name "Net-(D05-PadA)") (class "Default")
      (node (ref "D05") (pin "A") (pinfunction "A_A") (pintype "passive"))
      (node (ref "R6") (pin "2") (pinfunction "2_2") (pintype "passive"))
    )
    (net (code "42") (name "Net-(D06-PadA)") (class "Default")
      (node (ref "D06") (pin "A") (pinfunction "A_A") (pintype "passive"))
      (node (ref "R7") (pin "2") (pinfunction "2_2") (pintype "passive"))
    )
    (net (code "43") (name "Net-(D07-PadA)") (class "Default")
      (node (ref "D07") (pin "A") (pinfunction "A_A") (pintype "passive"))
      (node (ref "R8") (pin "2") (pinfunction "2_2") (pintype "passive"))
    )
    (net (code "44") (name "Net-(D08-PadA)") (class "Default")
      (node (ref "D08") (pin "A") (pinfunction "A_A") (pintype "passive"))
      (node (ref "R9") (pin "2") (pinfunction "2_2") (pintype "passive"))
    )
    (net (code "45") (name "Net-(D09-PadA)") (class "Default")
      (node (ref "D09") (pin "A") (pinfunction "A_A") (pintype "passive"))
      (node (ref "R10") (pin "2") (pinfunction "2_2") (pintype "passive"))
    )
    (net (code "46") (name "Net-(D10-PadA)") (class "Default")
      (node (ref "D10") (pin "A") (pinfunction "A_A") (pintype "passive"))
      (node (ref "R11") (pin "2") (pinfunction "2_2") (pintype "passive"))
    )
    (net (code "47") (name "Net-(D11-PadA)") (class "Default")
      (node (ref "D11") (pin "A") (pinfunction "A_A") (pintype "passive"))
      (node (ref "R12") (pin "2") (pinfunction "2_2") (pintype "passive"))
    )
    (net (code "48") (name "Net-(D12-PadA)") (class "Default")
      (node (ref "D12") (pin "A") (pinfunction "A_A") (pintype "passive"))
      (node (ref "R13") (pin "2") (pinfunction "2_2") (pintype "passive"))
    )
    (net (code "49") (name "Net-(D13-PadA)") (class "Default")
      (node (ref "D13") (pin "A") (pinfunction "A_A") (pintype "passive"))
      (node (ref "R14") (pin "2") (pinfunction "2_2") (pintype "passive"))
    )
    (net (code "50") (name "Net-(D14-PadA)") (class "Default")
      (node (ref "D14") (pin "A") (pinfunction "A_A") (pintype "passive"))
      (node (ref "R15") (pin "2") (pinfunction "2_2") (pintype "passive"))
    )
    (net (code "51") (name "Net-(D15-PadA)") (class "Default")
      (node (ref "D15") (pin "A") (pinfunction "A_A") (pintype "passive"))
      (node (ref "R16") (pin "2") (pinfunction "2_2") (pintype "passive"))
    )
    (net (code "52") (name "Net-(D16-C)") (class "Default")
      (node (ref "D16") (pin "K") (pinfunction "C_K") (pintype "passive"))
      (node (ref "D17") (pin "K") (pinfunction "C_K") (pintype "passive"))
      (node (ref "D18") (pin "K") (pinfunction "C_K") (pintype "passive"))
      (node (ref "D19") (pin "K") (pinfunction "C_K") (pintype "passive"))
      (node (ref "D20") (pin "K") (pinfunction "C_K") (pintype "passive"))
      (node (ref "D21") (pin "K") (pinfunction "C_K") (pintype "passive"))
      (node (ref "D22") (pin "K") (pinfunction "C_K") (pintype "passive"))
      (node (ref "D23") (pin "K") (pinfunction "C_K") (pintype "passive"))
      (node (ref "D24") (pin "K") (pinfunction "C_K") (pintype "passive"))
      (node (ref "D25") (pin "K") (pinfunction "C_K") (pintype "passive"))
      (node (ref "D26") (pin "K") (pinfunction "C_K") (pintype "passive"))
      (node (ref "D27") (pin "K") (pinfunction "C_K") (pintype "passive"))
      (node (ref "D28") (pin "K") (pinfunction "C_K") (pintype "passive"))
      (node (ref "D29") (pin "K") (pinfunction "C_K") (pintype "passive"))
      (node (ref "D30") (pin "K") (pinfunction "C_K") (pintype "passive"))
      (node (ref "D31") (pin "K") (pinfunction "C_K") (pintype "passive"))
      (node (ref "JP1C") (pin "5") (pinfunction "5_5") (pintype "passive"))
      (node (ref "JP1C") (pin "6") (pinfunction "6_6") (pintype "passive"))
      (node (ref "JP1D") (pin "5") (pinfunction "5_5") (pintype "passive"))
      (node (ref "JP1D") (pin "6") (pinfunction "6_6") (pintype "passive"))
    )
    (net (code "53") (name "Net-(D16-PadA)") (class "Default")
      (node (ref "D16") (pin "A") (pinfunction "A_A") (pintype "passive"))
      (node (ref "R17") (pin "2") (pinfunction "2_2") (pintype "passive"))
    )
    (net (code "54") (name "Net-(D17-PadA)") (class "Default")
      (node (ref "D17") (pin "A") (pinfunction "A_A") (pintype "passive"))
      (node (ref "R18") (pin "2") (pinfunction "2_2") (pintype "passive"))
    )
    (net (code "55") (name "Net-(D18-PadA)") (class "Default")
      (node (ref "D18") (pin "A") (pinfunction "A_A") (pintype "passive"))
      (node (ref "R19") (pin "2") (pinfunction "2_2") (pintype "passive"))
    )
    (net (code "56") (name "Net-(D19-PadA)") (class "Default")
      (node (ref "D19") (pin "A") (pinfunction "A_A") (pintype "passive"))
      (node (ref "R20") (pin "2") (pinfunction "2_2") (pintype "passive"))
    )
    (net (code "57") (name "Net-(D20-PadA)") (class "Default")
      (node (ref "D20") (pin "A") (pinfunction "A_A") (pintype "passive"))
      (node (ref "R21") (pin "2") (pinfunction "2_2") (pintype "passive"))
    )
    (net (code "58") (name "Net-(D21-PadA)") (class "Default")
      (node (ref "D21") (pin "A") (pinfunction "A_A") (pintype "passive"))
      (node (ref "R22") (pin "2") (pinfunction "2_2") (pintype "passive"))
    )
    (net (code "59") (name "Net-(D22-PadA)") (class "Default")
      (node (ref "D22") (pin "A") (pinfunction "A_A") (pintype "passive"))
      (node (ref "R23") (pin "2") (pinfunction "2_2") (pintype "passive"))
    )
    (net (code "60") (name "Net-(D23-PadA)") (class "Default")
      (node (ref "D23") (pin "A") (pinfunction "A_A") (pintype "passive"))
      (node (ref "R24") (pin "2") (pinfunction "2_2") (pintype "passive"))
    )
    (net (code "61") (name "Net-(D24-PadA)") (class "Default")
      (node (ref "D24") (pin "A") (pinfunction "A_A") (pintype "passive"))
      (node (ref "R25") (pin "2") (pinfunction "2_2") (pintype "passive"))
    )
    (net (code "62") (name "Net-(D25-PadA)") (class "Default")
      (node (ref "D25") (pin "A") (pinfunction "A_A") (pintype "passive"))
      (node (ref "R26") (pin "2") (pinfunction "2_2") (pintype "passive"))
    )
    (net (code "63") (name "Net-(D26-PadA)") (class "Default")
      (node (ref "D26") (pin "A") (pinfunction "A_A") (pintype "passive"))
      (node (ref "R27") (pin "2") (pinfunction "2_2") (pintype "passive"))
    )
    (net (code "64") (name "Net-(D27-PadA)") (class "Default")
      (node (ref "D27") (pin "A") (pinfunction "A_A") (pintype "passive"))
      (node (ref "R28") (pin "2") (pinfunction "2_2") (pintype "passive"))
    )
    (net (code "65") (name "Net-(D28-PadA)") (class "Default")
      (node (ref "D28") (pin "A") (pinfunction "A_A") (pintype "passive"))
      (node (ref "R29") (pin "2") (pinfunction "2_2") (pintype "passive"))
    )
    (net (code "66") (name "Net-(D29-PadA)") (class "Default")
      (node (ref "D29") (pin "A") (pinfunction "A_A") (pintype "passive"))
      (node (ref "R30") (pin "2") (pinfunction "2_2") (pintype "passive"))
    )
    (net (code "67") (name "Net-(D30-PadA)") (class "Default")
      (node (ref "D30") (pin "A") (pinfunction "A_A") (pintype "passive"))
      (node (ref "R31") (pin "2") (pinfunction "2_2") (pintype "passive"))
    )
    (net (code "68") (name "Net-(D31-PadA)") (class "Default")
      (node (ref "D31") (pin "A") (pinfunction "A_A") (pintype "passive"))
      (node (ref "R32") (pin "2") (pinfunction "2_2") (pintype "passive"))
    )
    (net (code "69") (name "Net-(JP1A-Pad1)") (class "Default")
      (node (ref "JP1A") (pin "1") (pinfunction "1_1") (pintype "passive"))
      (node (ref "R8") (pin "1") (pinfunction "1_1") (pintype "passive"))
    )
    (net (code "70") (name "Net-(JP1A-Pad2)") (class "Default")
      (node (ref "JP1A") (pin "2") (pinfunction "2_2") (pintype "passive"))
      (node (ref "R7") (pin "1") (pinfunction "1_1") (pintype "passive"))
    )
    (net (code "71") (name "Net-(JP1A-Pad3)") (class "Default")
      (node (ref "JP1A") (pin "3") (pinfunction "3_3") (pintype "passive"))
      (node (ref "R6") (pin "1") (pinfunction "1_1") (pintype "passive"))
    )
    (net (code "72") (name "Net-(JP1A-Pad4)") (class "Default")
      (node (ref "JP1A") (pin "4") (pinfunction "4_4") (pintype "passive"))
      (node (ref "R5") (pin "1") (pinfunction "1_1") (pintype "passive"))
    )
    (net (code "73") (name "Net-(JP1A-Pad7)") (class "Default")
      (node (ref "JP1A") (pin "7") (pinfunction "7_7") (pintype "passive"))
      (node (ref "R3") (pin "1") (pinfunction "1_1") (pintype "passive"))
    )
    (net (code "74") (name "Net-(JP1A-Pad8)") (class "Default")
      (node (ref "JP1A") (pin "8") (pinfunction "8_8") (pintype "passive"))
      (node (ref "R4") (pin "1") (pinfunction "1_1") (pintype "passive"))
    )
    (net (code "75") (name "Net-(JP1A-Pad9)") (class "Default")
      (node (ref "JP1A") (pin "9") (pinfunction "9_9") (pintype "passive"))
      (node (ref "R1") (pin "1") (pinfunction "1_1") (pintype "passive"))
    )
    (net (code "76") (name "Net-(JP1A-Pad10)") (class "Default")
      (node (ref "JP1A") (pin "10") (pinfunction "10_10") (pintype "passive"))
      (node (ref "R2") (pin "1") (pinfunction "1_1") (pintype "passive"))
    )
    (net (code "77") (name "Net-(JP1B-Pad1)") (class "Default")
      (node (ref "JP1B") (pin "1") (pinfunction "1_1") (pintype "passive"))
      (node (ref "R16") (pin "1") (pinfunction "1_1") (pintype "passive"))
    )
    (net (code "78") (name "Net-(JP1B-Pad2)") (class "Default")
      (node (ref "JP1B") (pin "2") (pinfunction "2_2") (pintype "passive"))
      (node (ref "R15") (pin "1") (pinfunction "1_1") (pintype "passive"))
    )
    (net (code "79") (name "Net-(JP1B-Pad3)") (class "Default")
      (node (ref "JP1B") (pin "3") (pinfunction "3_3") (pintype "passive"))
      (node (ref "R14") (pin "1") (pinfunction "1_1") (pintype "passive"))
    )
    (net (code "80") (name "Net-(JP1B-Pad4)") (class "Default")
      (node (ref "JP1B") (pin "4") (pinfunction "4_4") (pintype "passive"))
      (node (ref "R13") (pin "1") (pinfunction "1_1") (pintype "passive"))
    )
    (net (code "81") (name "Net-(JP1B-Pad7)") (class "Default")
      (node (ref "JP1B") (pin "7") (pinfunction "7_7") (pintype "passive"))
      (node (ref "R11") (pin "1") (pinfunction "1_1") (pintype "passive"))
    )
    (net (code "82") (name "Net-(JP1B-Pad8)") (class "Default")
      (node (ref "JP1B") (pin "8") (pinfunction "8_8") (pintype "passive"))
      (node (ref "R12") (pin "1") (pinfunction "1_1") (pintype "passive"))
    )
    (net (code "83") (name "Net-(JP1B-Pad9)") (class "Default")
      (node (ref "JP1B") (pin "9") (pinfunction "9_9") (pintype "passive"))
      (node (ref "R9") (pin "1") (pinfunction "1_1") (pintype "passive"))
    )
    (net (code "84") (name "Net-(JP1B-Pad10)") (class "Default")
      (node (ref "JP1B") (pin "10") (pinfunction "10_10") (pintype "passive"))
      (node (ref "R10") (pin "1") (pinfunction "1_1") (pintype "passive"))
    )
    (net (code "85") (name "Net-(JP1C-Pad1)") (class "Default")
      (node (ref "JP1C") (pin "1") (pinfunction "1_1") (pintype "passive"))
      (node (ref "R24") (pin "1") (pinfunction "1_1") (pintype "passive"))
    )
    (net (code "86") (name "Net-(JP1C-Pad2)") (class "Default")
      (node (ref "JP1C") (pin "2") (pinfunction "2_2") (pintype "passive"))
      (node (ref "R23") (pin "1") (pinfunction "1_1") (pintype "passive"))
    )
    (net (code "87") (name "Net-(JP1C-Pad3)") (class "Default")
      (node (ref "JP1C") (pin "3") (pinfunction "3_3") (pintype "passive"))
      (node (ref "R22") (pin "1") (pinfunction "1_1") (pintype "passive"))
    )
    (net (code "88") (name "Net-(JP1C-Pad4)") (class "Default")
      (node (ref "JP1C") (pin "4") (pinfunction "4_4") (pintype "passive"))
      (node (ref "R21") (pin "1") (pinfunction "1_1") (pintype "passive"))
    )
    (net (code "89") (name "Net-(JP1C-Pad7)") (class "Default")
      (node (ref "JP1C") (pin "7") (pinfunction "7_7") (pintype "passive"))
      (node (ref "R19") (pin "1") (pinfunction "1_1") (pintype "passive"))
    )
    (net (code "90") (name "Net-(JP1C-Pad8)") (class "Default")
      (node (ref "JP1C") (pin "8") (pinfunction "8_8") (pintype "passive"))
      (node (ref "R20") (pin "1") (pinfunction "1_1") (pintype "passive"))
    )
    (net (code "91") (name "Net-(JP1C-Pad9)") (class "Default")
      (node (ref "JP1C") (pin "9") (pinfunction "9_9") (pintype "passive"))
      (node (ref "R17") (pin "1") (pinfunction "1_1") (pintype "passive"))
    )
    (net (code "92") (name "Net-(JP1C-Pad10)") (class "Default")
      (node (ref "JP1C") (pin "10") (pinfunction "10_10") (pintype "passive"))
      (node (ref "R18") (pin "1") (pinfunction "1_1") (pintype "passive"))
    )
    (net (code "93") (name "Net-(JP1D-Pad1)") (class "Default")
      (node (ref "JP1D") (pin "1") (pinfunction "1_1") (pintype "passive"))
      (node (ref "R32") (pin "1") (pinfunction "1_1") (pintype "passive"))
    )
    (net (code "94") (name "Net-(JP1D-Pad2)") (class "Default")
      (node (ref "JP1D") (pin "2") (pinfunction "2_2") (pintype "passive"))
      (node (ref "R31") (pin "1") (pinfunction "1_1") (pintype "passive"))
    )
    (net (code "95") (name "Net-(JP1D-Pad3)") (class "Default")
      (node (ref "JP1D") (pin "3") (pinfunction "3_3") (pintype "passive"))
      (node (ref "R30") (pin "1") (pinfunction "1_1") (pintype "passive"))
    )
    (net (code "96") (name "Net-(JP1D-Pad4)") (class "Default")
      (node (ref "JP1D") (pin "4") (pinfunction "4_4") (pintype "passive"))
      (node (ref "R29") (pin "1") (pinfunction "1_1") (pintype "passive"))
    )
    (net (code "97") (name "Net-(JP1D-Pad7)") (class "Default")
      (node (ref "JP1D") (pin "7") (pinfunction "7_7") (pintype "passive"))
      (node (ref "R27") (pin "1") (pinfunction "1_1") (pintype "passive"))
    )
    (net (code "98") (name "Net-(JP1D-Pad8)") (class "Default")
      (node (ref "JP1D") (pin "8") (pinfunction "8_8") (pintype "passive"))
      (node (ref "R28") (pin "1") (pinfunction "1_1") (pintype "passive"))
    )
    (net (code "99") (name "Net-(JP1D-Pad9)") (class "Default")
      (node (ref "JP1D") (pin "9") (pinfunction "9_9") (pintype "passive"))
      (node (ref "R25") (pin "1") (pinfunction "1_1") (pintype "passive"))
    )
    (net (code "100") (name "Net-(JP1D-Pad10)") (class "Default")
      (node (ref "JP1D") (pin "10") (pinfunction "10_10") (pintype "passive"))
      (node (ref "R26") (pin "1") (pinfunction "1_1") (pintype "passive"))
    )
    (net (code "101") (name "Net-(JP2-Pad1)") (class "Default")
      (node (ref "JP2") (pin "1") (pinfunction "1_1") (pintype "passive"))
      (node (ref "R63") (pin "1") (pinfunction "1_1") (pintype "passive"))
    )
    (net (code "102") (name "Net-(JP2-Pad2)") (class "Default")
      (node (ref "JP2") (pin "2") (pinfunction "2_2") (pintype "passive"))
      (node (ref "R62") (pin "1") (pinfunction "1_1") (pintype "passive"))
    )
    (net (code "103") (name "Net-(JP2-Pad3)") (class "Default")
      (node (ref "JP2") (pin "3") (pinfunction "3_3") (pintype "passive"))
      (node (ref "R61") (pin "1") (pinfunction "1_1") (pintype "passive"))
    )
    (net (code "104") (name "Net-(JP2-Pad4)") (class "Default")
      (node (ref "JP2") (pin "4") (pinfunction "4_4") (pintype "passive"))
      (node (ref "R60") (pin "1") (pinfunction "1_1") (pintype "passive"))
    )
    (net (code "105") (name "Net-(JP2-Pad8)") (class "Default")
      (node (ref "JP2") (pin "8") (pinfunction "8_8") (pintype "passive"))
      (node (ref "R59") (pin "1") (pinfunction "1_1") (pintype "passive"))
    )
    (net (code "106") (name "Net-(JP2-Pad9)") (class "Default")
      (node (ref "JP2") (pin "9") (pinfunction "9_9") (pintype "passive"))
      (node (ref "R57") (pin "1") (pinfunction "1_1") (pintype "passive"))
    )
    (net (code "107") (name "Net-(JP2-Pad10)") (class "Default")
      (node (ref "JP2") (pin "10") (pinfunction "10_10") (pintype "passive"))
      (node (ref "R58") (pin "1") (pinfunction "1_1") (pintype "passive"))
    )
    (net (code "108") (name "Net-(JP3A-Pad1)") (class "Default")
      (node (ref "JP3A") (pin "1") (pinfunction "1_1") (pintype "passive"))
      (node (ref "R40") (pin "1") (pinfunction "1_1") (pintype "passive"))
    )
    (net (code "109") (name "Net-(JP3A-Pad2)") (class "Default")
      (node (ref "JP3A") (pin "2") (pinfunction "2_2") (pintype "passive"))
      (node (ref "R39") (pin "1") (pinfunction "1_1") (pintype "passive"))
    )
    (net (code "110") (name "Net-(JP3A-Pad3)") (class "Default")
      (node (ref "JP3A") (pin "3") (pinfunction "3_3") (pintype "passive"))
      (node (ref "R38") (pin "1") (pinfunction "1_1") (pintype "passive"))
    )
    (net (code "111") (name "Net-(JP3A-Pad4)") (class "Default")
      (node (ref "JP3A") (pin "4") (pinfunction "4_4") (pintype "passive"))
      (node (ref "R37") (pin "1") (pinfunction "1_1") (pintype "passive"))
    )
    (net (code "112") (name "Net-(JP3A-Pad7)") (class "Default")
      (node (ref "JP3A") (pin "7") (pinfunction "7_7") (pintype "passive"))
      (node (ref "R35") (pin "1") (pinfunction "1_1") (pintype "passive"))
    )
    (net (code "113") (name "Net-(JP3A-Pad8)") (class "Default")
      (node (ref "JP3A") (pin "8") (pinfunction "8_8") (pintype "passive"))
      (node (ref "R36") (pin "1") (pinfunction "1_1") (pintype "passive"))
    )
    (net (code "114") (name "Net-(JP3A-Pad9)") (class "Default")
      (node (ref "JP3A") (pin "9") (pinfunction "9_9") (pintype "passive"))
      (node (ref "R33") (pin "1") (pinfunction "1_1") (pintype "passive"))
    )
    (net (code "115") (name "Net-(JP3A-Pad10)") (class "Default")
      (node (ref "JP3A") (pin "10") (pinfunction "10_10") (pintype "passive"))
      (node (ref "R34") (pin "1") (pinfunction "1_1") (pintype "passive"))
    )
    (net (code "116") (name "Net-(JP3B-Pad1)") (class "Default")
      (node (ref "JP3B") (pin "1") (pinfunction "1_1") (pintype "passive"))
      (node (ref "R48") (pin "1") (pinfunction "1_1") (pintype "passive"))
    )
    (net (code "117") (name "Net-(JP3B-Pad2)") (class "Default")
      (node (ref "JP3B") (pin "2") (pinfunction "2_2") (pintype "passive"))
      (node (ref "R47") (pin "1") (pinfunction "1_1") (pintype "passive"))
    )
    (net (code "118") (name "Net-(JP3B-Pad3)") (class "Default")
      (node (ref "JP3B") (pin "3") (pinfunction "3_3") (pintype "passive"))
      (node (ref "R46") (pin "1") (pinfunction "1_1") (pintype "passive"))
    )
    (net (code "119") (name "Net-(JP3B-Pad4)") (class "Default")
      (node (ref "JP3B") (pin "4") (pinfunction "4_4") (pintype "passive"))
      (node (ref "R45") (pin "1") (pinfunction "1_1") (pintype "passive"))
    )
    (net (code "120") (name "Net-(JP3B-Pad7)") (class "Default")
      (node (ref "JP3B") (pin "7") (pinfunction "7_7") (pintype "passive"))
      (node (ref "R43") (pin "1") (pinfunction "1_1") (pintype "passive"))
    )
    (net (code "121") (name "Net-(JP3B-Pad8)") (class "Default")
      (node (ref "JP3B") (pin "8") (pinfunction "8_8") (pintype "passive"))
      (node (ref "R44") (pin "1") (pinfunction "1_1") (pintype "passive"))
    )
    (net (code "122") (name "Net-(JP3B-Pad9)") (class "Default")
      (node (ref "JP3B") (pin "9") (pinfunction "9_9") (pintype "passive"))
      (node (ref "R41") (pin "1") (pinfunction "1_1") (pintype "passive"))
    )
    (net (code "123") (name "Net-(JP3B-Pad10)") (class "Default")
      (node (ref "JP3B") (pin "10") (pinfunction "10_10") (pintype "passive"))
      (node (ref "R42") (pin "1") (pinfunction "1_1") (pintype "passive"))
    )
    (net (code "124") (name "Net-(JP3C-Pad1)") (class "Default")
      (node (ref "JP3C") (pin "1") (pinfunction "1_1") (pintype "passive"))
      (node (ref "R56") (pin "1") (pinfunction "1_1") (pintype "passive"))
    )
    (net (code "125") (name "Net-(JP3C-Pad2)") (class "Default")
      (node (ref "JP3C") (pin "2") (pinfunction "2_2") (pintype "passive"))
      (node (ref "R55") (pin "1") (pinfunction "1_1") (pintype "passive"))
    )
    (net (code "126") (name "Net-(JP3C-Pad3)") (class "Default")
      (node (ref "JP3C") (pin "3") (pinfunction "3_3") (pintype "passive"))
      (node (ref "R54") (pin "1") (pinfunction "1_1") (pintype "passive"))
    )
    (net (code "127") (name "Net-(JP3C-Pad4)") (class "Default")
      (node (ref "JP3C") (pin "4") (pinfunction "4_4") (pintype "passive"))
      (node (ref "R53") (pin "1") (pinfunction "1_1") (pintype "passive"))
    )
    (net (code "128") (name "Net-(JP3C-Pad7)") (class "Default")
      (node (ref "JP3C") (pin "7") (pinfunction "7_7") (pintype "passive"))
      (node (ref "R52") (pin "1") (pinfunction "1_1") (pintype "passive"))
    )
    (net (code "129") (name "Net-(JP3C-Pad8)") (class "Default")
      (node (ref "JP3C") (pin "8") (pinfunction "8_8") (pintype "passive"))
      (node (ref "R51") (pin "1") (pinfunction "1_1") (pintype "passive"))
    )
    (net (code "130") (name "Net-(JP3C-Pad9)") (class "Default")
      (node (ref "JP3C") (pin "9") (pinfunction "9_9") (pintype "passive"))
      (node (ref "R49") (pin "1") (pinfunction "1_1") (pintype "passive"))
    )
    (net (code "131") (name "Net-(JP3C-Pad10)") (class "Default")
      (node (ref "JP3C") (pin "10") (pinfunction "10_10") (pintype "passive"))
      (node (ref "R50") (pin "1") (pinfunction "1_1") (pintype "passive"))
    )
    (net (code "132") (name "Net-(JP4-Pad1)") (class "Default")
      (node (ref "JP4") (pin "1") (pinfunction "1_1") (pintype "passive"))
      (node (ref "R64") (pin "1") (pinfunction "1_1") (pintype "passive"))
    )
    (net (code "133") (name "Net-(JP4-Pad2)") (class "Default")
      (node (ref "JP4") (pin "2") (pinfunction "2_2") (pintype "passive"))
      (node (ref "R65") (pin "1") (pinfunction "1_1") (pintype "passive"))
    )
    (net (code "134") (name "Net-(JP4-Pad3)") (class "Default")
      (node (ref "JP4") (pin "3") (pinfunction "3_3") (pintype "passive"))
      (node (ref "R66") (pin "1") (pinfunction "1_1") (pintype "passive"))
    )
    (net (code "135") (name "Net-(JP4-Pad4)") (class "Default")
      (node (ref "JP4") (pin "4") (pinfunction "4_4") (pintype "passive"))
      (node (ref "R67") (pin "1") (pinfunction "1_1") (pintype "passive"))
    )
    (net (code "136") (name "Net-(JP4-Pad5)") (class "Default")
      (node (ref "JP4") (pin "5") (pinfunction "5_5") (pintype "passive"))
      (node (ref "R68") (pin "1") (pinfunction "1_1") (pintype "passive"))
    )
    (net (code "137") (name "Net-(JP4-Pad6)") (class "Default")
      (node (ref "JP4") (pin "6") (pinfunction "6_6") (pintype "passive"))
      (node (ref "R69") (pin "1") (pinfunction "1_1") (pintype "passive"))
    )
    (net (code "138") (name "Net-(JP4-Pad8)") (class "Default")
      (node (ref "JP4") (pin "8") (pinfunction "8_8") (pintype "passive"))
      (node (ref "R70") (pin "1") (pinfunction "1_1") (pintype "passive"))
    )
    (net (code "139") (name "Net-(JP4-Pad9)") (class "Default")
      (node (ref "JP4") (pin "9") (pinfunction "9_9") (pintype "passive"))
      (node (ref "R72") (pin "1") (pinfunction "1_1") (pintype "passive"))
    )
    (net (code "140") (name "Net-(JP4-Pad10)") (class "Default")
      (node (ref "JP4") (pin "10") (pinfunction "10_10") (pintype "passive"))
      (node (ref "R71") (pin "1") (pinfunction "1_1") (pintype "passive"))
    )
    (net (code "141") (name "Net-(JP4-Pad11)") (class "Default")
      (node (ref "JP4") (pin "11") (pinfunction "11_11") (pintype "passive"))
      (node (ref "R74") (pin "1") (pinfunction "1_1") (pintype "passive"))
    )
    (net (code "142") (name "Net-(JP4-Pad12)") (class "Default")
      (node (ref "JP4") (pin "12") (pinfunction "12_12") (pintype "passive"))
      (node (ref "R73") (pin "1") (pinfunction "1_1") (pintype "passive"))
    )
    (net (code "143") (name "Net-(JP4-Pad13)") (class "Default")
      (node (ref "JP4") (pin "13") (pinfunction "13_13") (pintype "passive"))
      (node (ref "R76") (pin "1") (pinfunction "1_1") (pintype "passive"))
    )
    (net (code "144") (name "Net-(JP4-Pad14)") (class "Default")
      (node (ref "JP4") (pin "14") (pinfunction "14_14") (pintype "passive"))
      (node (ref "R75") (pin "1") (pinfunction "1_1") (pintype "passive"))
    )
    (net (code "145") (name "Net-(R64-Pad2)") (class "Default")
      (node (ref "R64") (pin "2") (pinfunction "2_2") (pintype "passive"))
      (node (ref "S00") (pin "A") (pinfunction "A_A") (pintype "passive"))
    )
    (net (code "146") (name "Net-(R65-Pad2)") (class "Default")
      (node (ref "R65") (pin "2") (pinfunction "2_2") (pintype "passive"))
      (node (ref "S01") (pin "A") (pinfunction "A_A") (pintype "passive"))
    )
    (net (code "147") (name "Net-(R66-Pad2)") (class "Default")
      (node (ref "R66") (pin "2") (pinfunction "2_2") (pintype "passive"))
      (node (ref "S02") (pin "A") (pinfunction "A_A") (pintype "passive"))
    )
    (net (code "148") (name "Net-(R67-Pad2)") (class "Default")
      (node (ref "R67") (pin "2") (pinfunction "2_2") (pintype "passive"))
      (node (ref "S03") (pin "A") (pinfunction "A_A") (pintype "passive"))
    )
    (net (code "149") (name "Net-(R68-Pad2)") (class "Default")
      (node (ref "R68") (pin "2") (pinfunction "2_2") (pintype "passive"))
      (node (ref "S04") (pin "A") (pinfunction "A_A") (pintype "passive"))
    )
    (net (code "150") (name "Net-(R69-Pad2)") (class "Default")
      (node (ref "R69") (pin "2") (pinfunction "2_2") (pintype "passive"))
      (node (ref "S05") (pin "A") (pinfunction "A_A") (pintype "passive"))
    )
    (net (code "151") (name "Net-(R70-Pad2)") (class "Default")
      (node (ref "R70") (pin "2") (pinfunction "2_2") (pintype "passive"))
      (node (ref "S06") (pin "A") (pinfunction "A_A") (pintype "passive"))
    )
    (net (code "152") (name "Net-(R71-Pad2)") (class "Default")
      (node (ref "R71") (pin "2") (pinfunction "2_2") (pintype "passive"))
      (node (ref "S07") (pin "A") (pinfunction "A_A") (pintype "passive"))
    )
    (net (code "153") (name "Net-(R72-Pad2)") (class "Default")
      (node (ref "R72") (pin "2") (pinfunction "2_2") (pintype "passive"))
      (node (ref "S08") (pin "A") (pinfunction "A_A") (pintype "passive"))
    )
    (net (code "154") (name "Net-(R73-Pad2)") (class "Default")
      (node (ref "R73") (pin "2") (pinfunction "2_2") (pintype "passive"))
      (node (ref "S09") (pin "A") (pinfunction "A_A") (pintype "passive"))
    )
    (net (code "155") (name "Net-(R74-Pad2)") (class "Default")
      (node (ref "R74") (pin "2") (pinfunction "2_2") (pintype "passive"))
      (node (ref "S10") (pin "A") (pinfunction "A_A") (pintype "passive"))
    )
    (net (code "156") (name "Net-(R75-Pad2)") (class "Default")
      (node (ref "R75") (pin "2") (pinfunction "2_2") (pintype "passive"))
      (node (ref "S11") (pin "A") (pinfunction "A_A") (pintype "passive"))
    )
    (net (code "157") (name "Net-(R76-Pad2)") (class "Default")
      (node (ref "R76") (pin "2") (pinfunction "2_2") (pintype "passive"))
      (node (ref "S12") (pin "A") (pinfunction "A_A") (pintype "passive"))
    )
    (net (code "158") (name "Net-(S00-C)") (class "Default")
      (node (ref "JP4") (pin "7") (pinfunction "7_7") (pintype "passive"))
      (node (ref "S00") (pin "K") (pinfunction "C_K") (pintype "passive"))
      (node (ref "S01") (pin "K") (pinfunction "C_K") (pintype "passive"))
      (node (ref "S02") (pin "K") (pinfunction "C_K") (pintype "passive"))
      (node (ref "S03") (pin "K") (pinfunction "C_K") (pintype "passive"))
      (node (ref "S04") (pin "K") (pinfunction "C_K") (pintype "passive"))
      (node (ref "S05") (pin "K") (pinfunction "C_K") (pintype "passive"))
      (node (ref "S06") (pin "K") (pinfunction "C_K") (pintype "passive"))
      (node (ref "S07") (pin "K") (pinfunction "C_K") (pintype "passive"))
      (node (ref "S08") (pin "K") (pinfunction "C_K") (pintype "passive"))
      (node (ref "S09") (pin "K") (pinfunction "C_K") (pintype "passive"))
      (node (ref "S10") (pin "K") (pinfunction "C_K") (pintype "passive"))
      (node (ref "S11") (pin "K") (pinfunction "C_K") (pintype "passive"))
      (node (ref "S12") (pin "K") (pinfunction "C_K") (pintype "passive"))
    )
    (net (code "159") (name "unconnected-(JP2-Pad7)") (class "Default")
      (node (ref "JP2") (pin "7") (pinfunction "7_7") (pintype "passive"))
    )
  )
)
